# controller.net
KiCad netlist of a schematic drawn in EAGLE
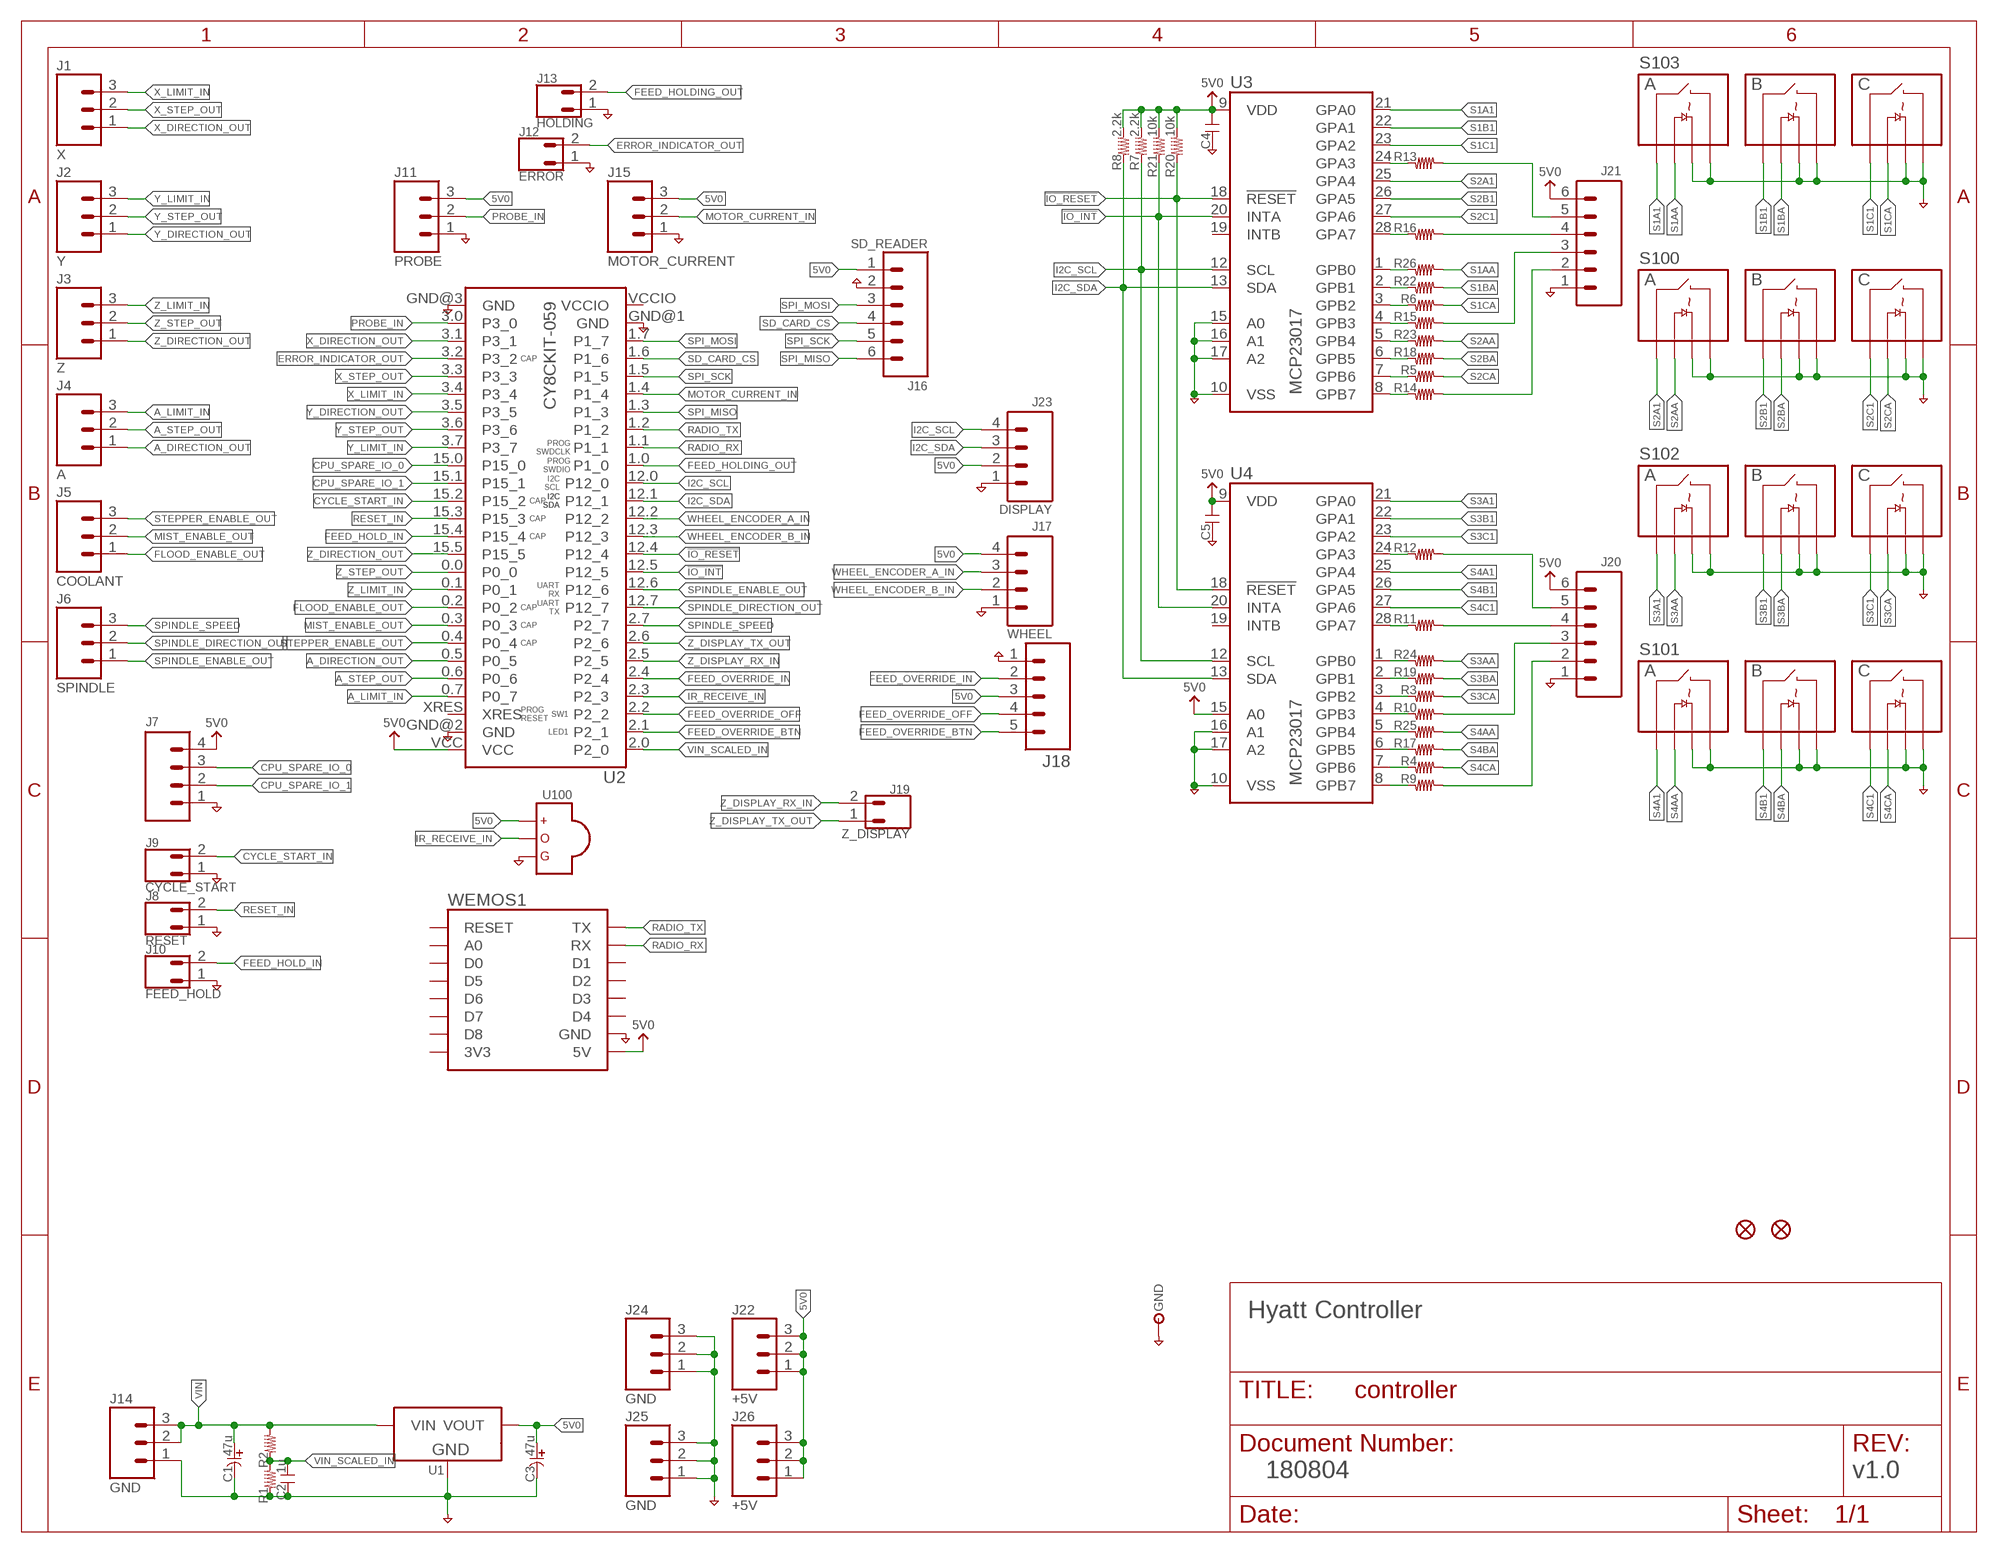
[diagram p0: schematic, sheet 1]

(export (version "E")
  (design (tool "Eeschema 10.0.6"))
  (components
    (comp (ref "C1")
      (value "47u")
      (footprint "eagle-import:E5-10")
      (libsource (lib "eagle-import") (part "C-POLARIZED-E5-10"))
    )
    (comp (ref "C2")
      (value "1u")
      (footprint "eagle-import:C0603")
      (libsource (lib "eagle-import") (part "C-0603"))
    )
    (comp (ref "C3")
      (value "47u")
      (footprint "eagle-import:E5-10")
      (libsource (lib "eagle-import") (part "C-POLARIZED-E5-10"))
    )
    (comp (ref "C4")
      (value "C-0603")
      (footprint "eagle-import:C0603")
      (libsource (lib "eagle-import") (part "C-0603"))
    )
    (comp (ref "C5")
      (value "C-0603")
      (footprint "eagle-import:C0603")
      (libsource (lib "eagle-import") (part "C-0603"))
    )
    (comp (ref "FID1")
      (value "FIDUCIAL1.5X3")
      (footprint "eagle-import:FIDUCIAL-1.5X3")
      (libsource (lib "eagle-import") (part "FIDUCIAL1.5X3"))
    )
    (comp (ref "FID2")
      (value "FIDUCIAL1.5X3")
      (footprint "eagle-import:FIDUCIAL-1.5X3")
      (libsource (lib "eagle-import") (part "FIDUCIAL1.5X3"))
    )
    (comp (ref "GND")
      (value "TESTPOINTTHRU")
      (footprint "eagle-import:TPTHRU")
      (libsource (lib "eagle-import") (part "TESTPOINTTHRU"))
    )
    (comp (ref "J1")
      (value "X")
      (footprint "eagle-import:CONN-3.81MM-KF2EDG-3")
      (libsource (lib "eagle-import") (part "CONN-03-3.81MM-PLUGIN-SCREW"))
    )
    (comp (ref "J2")
      (value "Y")
      (footprint "eagle-import:CONN-3.81MM-KF2EDG-3")
      (libsource (lib "eagle-import") (part "CONN-03-3.81MM-PLUGIN-SCREW"))
    )
    (comp (ref "J3")
      (value "Z")
      (footprint "eagle-import:CONN-3.81MM-KF2EDG-3")
      (libsource (lib "eagle-import") (part "CONN-03-3.81MM-PLUGIN-SCREW"))
    )
    (comp (ref "J4")
      (value "A")
      (footprint "eagle-import:CONN-3.81MM-KF2EDG-3")
      (libsource (lib "eagle-import") (part "CONN-03-3.81MM-PLUGIN-SCREW"))
    )
    (comp (ref "J5")
      (value "COOLANT")
      (footprint "eagle-import:CONN-3.81MM-KF2EDG-3")
      (libsource (lib "eagle-import") (part "CONN-03-3.81MM-PLUGIN-SCREW"))
    )
    (comp (ref "J6")
      (value "SPINDLE")
      (footprint "eagle-import:CONN-3.81MM-KF2EDG-3")
      (libsource (lib "eagle-import") (part "CONN-03-3.81MM-PLUGIN-SCREW"))
    )
    (comp (ref "J7")
      (value "CONN-04-0.1")
      (footprint "eagle-import:1X04")
      (libsource (lib "eagle-import") (part "CONN-04-0.1"))
    )
    (comp (ref "J8")
      (value "RESET")
      (footprint "eagle-import:CONN-.100-2")
      (libsource (lib "eagle-import") (part "CONN-02-.100-VERT-HEADER"))
    )
    (comp (ref "J9")
      (value "CYCLE_START")
      (footprint "eagle-import:CONN-.100-2")
      (libsource (lib "eagle-import") (part "CONN-02-.100-VERT-HEADER"))
    )
    (comp (ref "J10")
      (value "FEED_HOLD")
      (footprint "eagle-import:CONN-.100-2")
      (libsource (lib "eagle-import") (part "CONN-02-.100-VERT-HEADER"))
    )
    (comp (ref "J11")
      (value "PROBE")
      (footprint "eagle-import:CONN-3.81MM-KF2EDG-3")
      (libsource (lib "eagle-import") (part "CONN-03-3.81MM-PLUGIN-SCREW"))
    )
    (comp (ref "J12")
      (value "ERROR")
      (footprint "eagle-import:CONN-.100-2")
      (libsource (lib "eagle-import") (part "CONN-02-.100-VERT-HEADER"))
    )
    (comp (ref "J13")
      (value "HOLDING")
      (footprint "eagle-import:CONN-.100-2")
      (libsource (lib "eagle-import") (part "CONN-02-.100-VERT-HEADER"))
    )
    (comp (ref "J14")
      (value "GND")
      (footprint "eagle-import:CONN-3.81MM-KF2EDG-3")
      (libsource (lib "eagle-import") (part "CONN-03-3.81MM-PLUGIN-SCREW"))
    )
    (comp (ref "J15")
      (value "MOTOR_CURRENT")
      (footprint "eagle-import:CONN-3.81MM-KF2EDG-3")
      (libsource (lib "eagle-import") (part "CONN-03-3.81MM-PLUGIN-SCREW"))
    )
    (comp (ref "J16")
      (value "SD_READER")
      (footprint "eagle-import:1X06")
      (libsource (lib "eagle-import") (part "CONN-06-0.1"))
    )
    (comp (ref "J17")
      (value "WHEEL")
      (footprint "eagle-import:CONN-.100-4")
      (libsource (lib "eagle-import") (part "CONN-04-.100-VERT-HEADER"))
    )
    (comp (ref "J18")
      (value "CONN-05-PTH")
      (footprint "eagle-import:1X05")
      (libsource (lib "eagle-import") (part "CONN-05-PTH"))
    )
    (comp (ref "J19")
      (value "Z_DISPLAY")
      (footprint "eagle-import:CONN-3.81MM-KF2EDG-2")
      (libsource (lib "eagle-import") (part "CONN-02-3.81MM-PLUGIN-SCREW"))
    )
    (comp (ref "J20")
      (value "CONN-06-.100-VERT-HEADER")
      (footprint "eagle-import:CONN-.100-6")
      (libsource (lib "eagle-import") (part "CONN-06-.100-VERT-HEADER"))
    )
    (comp (ref "J21")
      (value "CONN-06-.100-VERT-HEADER")
      (footprint "eagle-import:CONN-.100-6")
      (libsource (lib "eagle-import") (part "CONN-06-.100-VERT-HEADER"))
    )
    (comp (ref "J22")
      (value "+5V")
      (footprint "eagle-import:CONN-3.81MM-KF2EDG-3")
      (libsource (lib "eagle-import") (part "CONN-03-3.81MM-PLUGIN-SCREW"))
    )
    (comp (ref "J23")
      (value "DISPLAY")
      (footprint "eagle-import:CONN-.100-4")
      (libsource (lib "eagle-import") (part "CONN-04-.100-VERT-HEADER"))
    )
    (comp (ref "J24")
      (value "GND")
      (footprint "eagle-import:CONN-3.81MM-KF2EDG-3")
      (libsource (lib "eagle-import") (part "CONN-03-3.81MM-PLUGIN-SCREW"))
    )
    (comp (ref "J25")
      (value "GND")
      (footprint "eagle-import:CONN-3.81MM-KF2EDG-3")
      (libsource (lib "eagle-import") (part "CONN-03-3.81MM-PLUGIN-SCREW"))
    )
    (comp (ref "J26")
      (value "+5V")
      (footprint "eagle-import:CONN-3.81MM-KF2EDG-3")
      (libsource (lib "eagle-import") (part "CONN-03-3.81MM-PLUGIN-SCREW"))
    )
    (comp (ref "R1")
      (value "R-0603")
      (footprint "eagle-import:R0603")
      (libsource (lib "eagle-import") (part "R-0603"))
    )
    (comp (ref "R2")
      (value "R-0603")
      (footprint "eagle-import:R0603")
      (libsource (lib "eagle-import") (part "R-0603"))
    )
    (comp (ref "R3")
      (value "R-0603")
      (footprint "eagle-import:R0603")
      (libsource (lib "eagle-import") (part "R-0603"))
    )
    (comp (ref "R4")
      (value "R-0603")
      (footprint "eagle-import:R0603")
      (libsource (lib "eagle-import") (part "R-0603"))
    )
    (comp (ref "R5")
      (value "R-0603")
      (footprint "eagle-import:R0603")
      (libsource (lib "eagle-import") (part "R-0603"))
    )
    (comp (ref "R6")
      (value "R-0603")
      (footprint "eagle-import:R0603")
      (libsource (lib "eagle-import") (part "R-0603"))
    )
    (comp (ref "R7")
      (value "2.2k")
      (footprint "eagle-import:R0603")
      (libsource (lib "eagle-import") (part "R-0603"))
    )
    (comp (ref "R8")
      (value "2.2k")
      (footprint "eagle-import:R0603")
      (libsource (lib "eagle-import") (part "R-0603"))
    )
    (comp (ref "R9")
      (value "R-0603")
      (footprint "eagle-import:R0603")
      (libsource (lib "eagle-import") (part "R-0603"))
    )
    (comp (ref "R10")
      (value "R-0603")
      (footprint "eagle-import:R0603")
      (libsource (lib "eagle-import") (part "R-0603"))
    )
    (comp (ref "R11")
      (value "R-0603")
      (footprint "eagle-import:R0603")
      (libsource (lib "eagle-import") (part "R-0603"))
    )
    (comp (ref "R12")
      (value "R-0603")
      (footprint "eagle-import:R0603")
      (libsource (lib "eagle-import") (part "R-0603"))
    )
    (comp (ref "R13")
      (value "R-0603")
      (footprint "eagle-import:R0603")
      (libsource (lib "eagle-import") (part "R-0603"))
    )
    (comp (ref "R14")
      (value "R-0603")
      (footprint "eagle-import:R0603")
      (libsource (lib "eagle-import") (part "R-0603"))
    )
    (comp (ref "R15")
      (value "R-0603")
      (footprint "eagle-import:R0603")
      (libsource (lib "eagle-import") (part "R-0603"))
    )
    (comp (ref "R16")
      (value "R-0603")
      (footprint "eagle-import:R0603")
      (libsource (lib "eagle-import") (part "R-0603"))
    )
    (comp (ref "R17")
      (value "R-0603")
      (footprint "eagle-import:R0603")
      (libsource (lib "eagle-import") (part "R-0603"))
    )
    (comp (ref "R18")
      (value "R-0603")
      (footprint "eagle-import:R0603")
      (libsource (lib "eagle-import") (part "R-0603"))
    )
    (comp (ref "R19")
      (value "R-0603")
      (footprint "eagle-import:R0603")
      (libsource (lib "eagle-import") (part "R-0603"))
    )
    (comp (ref "R20")
      (value "10k")
      (footprint "eagle-import:R0603")
      (libsource (lib "eagle-import") (part "R-0603"))
    )
    (comp (ref "R21")
      (value "10k")
      (footprint "eagle-import:R0603")
      (libsource (lib "eagle-import") (part "R-0603"))
    )
    (comp (ref "R22")
      (value "R-0603")
      (footprint "eagle-import:R0603")
      (libsource (lib "eagle-import") (part "R-0603"))
    )
    (comp (ref "R23")
      (value "R-0603")
      (footprint "eagle-import:R0603")
      (libsource (lib "eagle-import") (part "R-0603"))
    )
    (comp (ref "R24")
      (value "R-0603")
      (footprint "eagle-import:R0603")
      (libsource (lib "eagle-import") (part "R-0603"))
    )
    (comp (ref "R25")
      (value "R-0603")
      (footprint "eagle-import:R0603")
      (libsource (lib "eagle-import") (part "R-0603"))
    )
    (comp (ref "R26")
      (value "R-0603")
      (footprint "eagle-import:R0603")
      (libsource (lib "eagle-import") (part "R-0603"))
    )
    (comp (ref "S100")
      (value "SWITCH-DTMF-3-LED")
      (footprint "eagle-import:SWITCH-DTMF-3-LED")
      (libsource (lib "eagle-import") (part "SWITCH-DTMF-3-LED"))
    )
    (comp (ref "S101")
      (value "SWITCH-DTMF-3-LED")
      (footprint "eagle-import:SWITCH-DTMF-3-LED")
      (libsource (lib "eagle-import") (part "SWITCH-DTMF-3-LED"))
    )
    (comp (ref "S102")
      (value "SWITCH-DTMF-3-LED")
      (footprint "eagle-import:SWITCH-DTMF-3-LED")
      (libsource (lib "eagle-import") (part "SWITCH-DTMF-3-LED"))
    )
    (comp (ref "S103")
      (value "SWITCH-DTMF-3-LED")
      (footprint "eagle-import:SWITCH-DTMF-3-LED")
      (libsource (lib "eagle-import") (part "SWITCH-DTMF-3-LED"))
    )
    (comp (ref "U1")
      (value "VREG-SIP3")
      (footprint "eagle-import:VREG-SIP3")
      (libsource (lib "eagle-import") (part "VREG-SIP3"))
    )
    (comp (ref "U2")
      (value "BOARD-PSOC-CY8CKIT-059")
      (footprint "eagle-import:BOARD-PSOC-CY8CKIT-059")
      (libsource (lib "eagle-import") (part "BOARD-PSOC-CY8CKIT-059"))
    )
    (comp (ref "U3")
      (value "IO-MCP23017SO")
      (footprint "eagle-import:SO28W")
      (fields (field (name "MF") "MICROCHIP") (field (name "MPN") "MCP23017-E/SO"))
      (libsource (lib "eagle-import") (part "IO-MCP23017SO"))
    )
    (comp (ref "U4")
      (value "IO-MCP23017SO")
      (footprint "eagle-import:SO28W")
      (fields (field (name "MF") "MICROCHIP") (field (name "MPN") "MCP23017-E/SO"))
      (libsource (lib "eagle-import") (part "IO-MCP23017SO"))
    )
    (comp (ref "U100")
      (value "SENSOR-IR-THRU")
      (footprint "eagle-import:IRDETECTOR-THRU")
      (libsource (lib "eagle-import") (part "SENSOR-IR-THRU"))
    )
    (comp (ref "WEMOS1")
      (value "RADIO-WEMOS-D1-MINI")
      (footprint "eagle-import:WEMOS-D1-MINI")
      (libsource (lib "eagle-import") (part "RADIO-WEMOS-D1-MINI"))
    )
  )
  (nets
    (net (code "1") (name "/~{IO_INT}") (class "Default")
      (node (ref "R21") (pin "1") (pinfunction "1_1") (pintype "passive"))
      (node (ref "U2") (pin "12.5") (pinfunction "P12_5_12.5") (pintype "bidirectional"))
      (node (ref "U3") (pin "20") (pinfunction "INTA_20") (pintype "output"))
      (node (ref "U4") (pin "20") (pinfunction "INTA_20") (pintype "output"))
    )
    (net (code "2") (name "/~{IO_RESET}") (class "Default")
      (node (ref "R20") (pin "1") (pinfunction "1_1") (pintype "passive"))
      (node (ref "U2") (pin "12.4") (pinfunction "P12_4_12.4") (pintype "bidirectional"))
      (node (ref "U3") (pin "18") (pinfunction "~{RESET}_18") (pintype "input"))
      (node (ref "U4") (pin "18") (pinfunction "~{RESET}_18") (pintype "input"))
    )
    (net (code "3") (name "5V0") (class "Default")
      (node (ref "C3") (pin "+") (pinfunction "+_+") (pintype "passive"))
      (node (ref "C4") (pin "1") (pinfunction "1_1") (pintype "passive"))
      (node (ref "C5") (pin "1") (pinfunction "1_1") (pintype "passive"))
      (node (ref "J11") (pin "3") (pinfunction "3_3") (pintype "passive"))
      (node (ref "J15") (pin "3") (pinfunction "3_3") (pintype "passive"))
      (node (ref "J16") (pin "1") (pinfunction "1_1") (pintype "passive"))
      (node (ref "J17") (pin "4") (pinfunction "4_4") (pintype "passive"))
      (node (ref "J18") (pin "3") (pinfunction "3_3") (pintype "passive"))
      (node (ref "J20") (pin "6") (pinfunction "6_6") (pintype "passive"))
      (node (ref "J21") (pin "6") (pinfunction "6_6") (pintype "passive"))
      (node (ref "J22") (pin "1") (pinfunction "1_1") (pintype "passive"))
      (node (ref "J22") (pin "2") (pinfunction "2_2") (pintype "passive"))
      (node (ref "J22") (pin "3") (pinfunction "3_3") (pintype "passive"))
      (node (ref "J23") (pin "2") (pinfunction "2_2") (pintype "passive"))
      (node (ref "J26") (pin "1") (pinfunction "1_1") (pintype "passive"))
      (node (ref "J26") (pin "2") (pinfunction "2_2") (pintype "passive"))
      (node (ref "J26") (pin "3") (pinfunction "3_3") (pintype "passive"))
      (node (ref "J7") (pin "4") (pinfunction "4_4") (pintype "passive"))
      (node (ref "R20") (pin "2") (pinfunction "2_2") (pintype "passive"))
      (node (ref "R21") (pin "2") (pinfunction "2_2") (pintype "passive"))
      (node (ref "R7") (pin "2") (pinfunction "2_2") (pintype "passive"))
      (node (ref "R8") (pin "2") (pinfunction "2_2") (pintype "passive"))
      (node (ref "U1") (pin "3") (pinfunction "VOUT_3") (pintype "bidirectional"))
      (node (ref "U100") (pin "VCC") (pinfunction "VCC_VCC") (pintype "bidirectional"))
      (node (ref "U2") (pin "VCC") (pinfunction "VCC_VCC") (pintype "bidirectional"))
      (node (ref "U3") (pin "9") (pinfunction "VDD_9") (pintype "power_in"))
      (node (ref "U4") (pin "15") (pinfunction "A0_15") (pintype "input"))
      (node (ref "U4") (pin "9") (pinfunction "VDD_9") (pintype "power_in"))
      (node (ref "WEMOS1") (pin "5V") (pinfunction "5V_5V") (pintype "bidirectional"))
    )
    (net (code "4") (name "A_DIRECTION_OUT") (class "Default")
      (node (ref "J4") (pin "1") (pinfunction "1_1") (pintype "passive"))
      (node (ref "U2") (pin "0.5") (pinfunction "P0_5_0.5") (pintype "bidirectional"))
    )
    (net (code "5") (name "A_LIMIT_IN") (class "Default")
      (node (ref "J4") (pin "3") (pinfunction "3_3") (pintype "passive"))
      (node (ref "U2") (pin "0.7") (pinfunction "P0_7_0.7") (pintype "bidirectional"))
    )
    (net (code "6") (name "A_STEP_OUT") (class "Default")
      (node (ref "J4") (pin "2") (pinfunction "2_2") (pintype "passive"))
      (node (ref "U2") (pin "0.6") (pinfunction "P0_6_0.6") (pintype "bidirectional"))
    )
    (net (code "7") (name "CPU_SPARE_IO_0") (class "Default")
      (node (ref "J7") (pin "3") (pinfunction "3_3") (pintype "passive"))
      (node (ref "U2") (pin "15.0") (pinfunction "P15_0_15.0") (pintype "bidirectional"))
    )
    (net (code "8") (name "CPU_SPARE_IO_1") (class "Default")
      (node (ref "J7") (pin "2") (pinfunction "2_2") (pintype "passive"))
      (node (ref "U2") (pin "15.1") (pinfunction "P15_1_15.1") (pintype "bidirectional"))
    )
    (net (code "9") (name "CYCLE_START_IN") (class "Default")
      (node (ref "J9") (pin "2") (pinfunction "2_2") (pintype "passive"))
      (node (ref "U2") (pin "15.2") (pinfunction "P15_2_15.2") (pintype "bidirectional"))
    )
    (net (code "10") (name "ERROR_INDICATOR_OUT") (class "Default")
      (node (ref "J12") (pin "2") (pinfunction "2_2") (pintype "passive"))
      (node (ref "U2") (pin "3.2") (pinfunction "P3_2_3.2") (pintype "bidirectional"))
    )
    (net (code "11") (name "FEED_HOLDING_OUT") (class "Default")
      (node (ref "J13") (pin "2") (pinfunction "2_2") (pintype "passive"))
      (node (ref "U2") (pin "1.0") (pinfunction "P1_0_1.0") (pintype "bidirectional"))
    )
    (net (code "12") (name "FEED_HOLD_IN") (class "Default")
      (node (ref "J10") (pin "2") (pinfunction "2_2") (pintype "passive"))
      (node (ref "U2") (pin "15.4") (pinfunction "P15_4_15.4") (pintype "bidirectional"))
    )
    (net (code "13") (name "FEED_OVERRIDE_BTN") (class "Default")
      (node (ref "J18") (pin "5") (pinfunction "5_5") (pintype "passive"))
      (node (ref "U2") (pin "2.1") (pinfunction "P2_1_2.1") (pintype "bidirectional"))
    )
    (net (code "14") (name "FEED_OVERRIDE_IN") (class "Default")
      (node (ref "J18") (pin "2") (pinfunction "2_2") (pintype "passive"))
      (node (ref "U2") (pin "2.4") (pinfunction "P2_4_2.4") (pintype "bidirectional"))
    )
    (net (code "15") (name "FEED_OVERRIDE_OFF") (class "Default")
      (node (ref "J18") (pin "4") (pinfunction "4_4") (pintype "passive"))
      (node (ref "U2") (pin "2.2") (pinfunction "P2_2_2.2") (pintype "bidirectional"))
    )
    (net (code "16") (name "FLOOD_ENABLE_OUT") (class "Default")
      (node (ref "J5") (pin "1") (pinfunction "1_1") (pintype "passive"))
      (node (ref "U2") (pin "0.2") (pinfunction "P0_2_0.2") (pintype "bidirectional"))
    )
    (net (code "17") (name "GND") (class "Default")
      (node (ref "C1") (pin "-") (pinfunction "-_-") (pintype "passive"))
      (node (ref "C2") (pin "2") (pinfunction "2_2") (pintype "passive"))
      (node (ref "C3") (pin "-") (pinfunction "-_-") (pintype "passive"))
      (node (ref "C4") (pin "2") (pinfunction "2_2") (pintype "passive"))
      (node (ref "C5") (pin "2") (pinfunction "2_2") (pintype "passive"))
      (node (ref "GND") (pin "1") (pinfunction "P$1_1") (pintype "bidirectional"))
      (node (ref "J10") (pin "1") (pinfunction "1_1") (pintype "passive"))
      (node (ref "J11") (pin "1") (pinfunction "1_1") (pintype "passive"))
      (node (ref "J12") (pin "1") (pinfunction "1_1") (pintype "passive"))
      (node (ref "J13") (pin "1") (pinfunction "1_1") (pintype "passive"))
      (node (ref "J14") (pin "1") (pinfunction "1_1") (pintype "passive"))
      (node (ref "J15") (pin "1") (pinfunction "1_1") (pintype "passive"))
      (node (ref "J16") (pin "2") (pinfunction "2_2") (pintype "passive"))
      (node (ref "J17") (pin "1") (pinfunction "1_1") (pintype "passive"))
      (node (ref "J18") (pin "1") (pinfunction "1_1") (pintype "passive"))
      (node (ref "J20") (pin "1") (pinfunction "1_1") (pintype "passive"))
      (node (ref "J21") (pin "1") (pinfunction "1_1") (pintype "passive"))
      (node (ref "J23") (pin "1") (pinfunction "1_1") (pintype "passive"))
      (node (ref "J24") (pin "1") (pinfunction "1_1") (pintype "passive"))
      (node (ref "J24") (pin "2") (pinfunction "2_2") (pintype "passive"))
      (node (ref "J24") (pin "3") (pinfunction "3_3") (pintype "passive"))
      (node (ref "J25") (pin "1") (pinfunction "1_1") (pintype "passive"))
      (node (ref "J25") (pin "2") (pinfunction "2_2") (pintype "passive"))
      (node (ref "J25") (pin "3") (pinfunction "3_3") (pintype "passive"))
      (node (ref "J7") (pin "1") (pinfunction "1_1") (pintype "passive"))
      (node (ref "J8") (pin "1") (pinfunction "1_1") (pintype "passive"))
      (node (ref "J9") (pin "1") (pinfunction "1_1") (pintype "passive"))
      (node (ref "R1") (pin "1") (pinfunction "1_1") (pintype "passive"))
      (node (ref "S100") (pin "A_2") (pinfunction "A_2_A_2") (pintype "bidirectional"))
      (node (ref "S100") (pin "A_C") (pinfunction "A_C_A_C") (pintype "bidirectional"))
      (node (ref "S100") (pin "B_2") (pinfunction "B_2_B_2") (pintype "bidirectional"))
      (node (ref "S100") (pin "B_C") (pinfunction "B_C_B_C") (pintype "bidirectional"))
      (node (ref "S100") (pin "C_2") (pinfunction "C_2_C_2") (pintype "bidirectional"))
      (node (ref "S100") (pin "C_C") (pinfunction "C_C_C_C") (pintype "bidirectional"))
      (node (ref "S101") (pin "A_2") (pinfunction "A_2_A_2") (pintype "bidirectional"))
      (node (ref "S101") (pin "A_C") (pinfunction "A_C_A_C") (pintype "bidirectional"))
      (node (ref "S101") (pin "B_2") (pinfunction "B_2_B_2") (pintype "bidirectional"))
      (node (ref "S101") (pin "B_C") (pinfunction "B_C_B_C") (pintype "bidirectional"))
      (node (ref "S101") (pin "C_2") (pinfunction "C_2_C_2") (pintype "bidirectional"))
      (node (ref "S101") (pin "C_C") (pinfunction "C_C_C_C") (pintype "bidirectional"))
      (node (ref "S102") (pin "A_2") (pinfunction "A_2_A_2") (pintype "bidirectional"))
      (node (ref "S102") (pin "A_C") (pinfunction "A_C_A_C") (pintype "bidirectional"))
      (node (ref "S102") (pin "B_2") (pinfunction "B_2_B_2") (pintype "bidirectional"))
      (node (ref "S102") (pin "B_C") (pinfunction "B_C_B_C") (pintype "bidirectional"))
      (node (ref "S102") (pin "C_2") (pinfunction "C_2_C_2") (pintype "bidirectional"))
      (node (ref "S102") (pin "C_C") (pinfunction "C_C_C_C") (pintype "bidirectional"))
      (node (ref "S103") (pin "A_2") (pinfunction "A_2_A_2") (pintype "bidirectional"))
      (node (ref "S103") (pin "A_C") (pinfunction "A_C_A_C") (pintype "bidirectional"))
      (node (ref "S103") (pin "B_2") (pinfunction "B_2_B_2") (pintype "bidirectional"))
      (node (ref "S103") (pin "B_C") (pinfunction "B_C_B_C") (pintype "bidirectional"))
      (node (ref "S103") (pin "C_2") (pinfunction "C_2_C_2") (pintype "bidirectional"))
      (node (ref "S103") (pin "C_C") (pinfunction "C_C_C_C") (pintype "bidirectional"))
      (node (ref "U1") (pin "2") (pinfunction "GND_2") (pintype "bidirectional"))
      (node (ref "U100") (pin "GND") (pinfunction "GND_GND") (pintype "bidirectional"))
      (node (ref "U2") (pin "GND@1") (pinfunction "GND_GND@1") (pintype "bidirectional"))
      (node (ref "U2") (pin "GND@2") (pinfunction "GND_GND@2") (pintype "bidirectional"))
      (node (ref "U2") (pin "GND@3") (pinfunction "GND_GND@3") (pintype "bidirectional"))
      (node (ref "U3") (pin "10") (pinfunction "VSS_10") (pintype "power_in"))
      (node (ref "U3") (pin "15") (pinfunction "A0_15") (pintype "input"))
      (node (ref "U3") (pin "16") (pinfunction "A1_16") (pintype "input"))
      (node (ref "U3") (pin "17") (pinfunction "A2_17") (pintype "input"))
      (node (ref "U4") (pin "10") (pinfunction "VSS_10") (pintype "power_in"))
      (node (ref "U4") (pin "16") (pinfunction "A1_16") (pintype "input"))
      (node (ref "U4") (pin "17") (pinfunction "A2_17") (pintype "input"))
      (node (ref "WEMOS1") (pin "GND") (pinfunction "GND_GND") (pintype "bidirectional"))
    )
    (net (code "18") (name "I2C_SCL") (class "Default")
      (node (ref "J23") (pin "4") (pinfunction "4_4") (pintype "passive"))
      (node (ref "R7") (pin "1") (pinfunction "1_1") (pintype "passive"))
      (node (ref "U2") (pin "12.0") (pinfunction "P12_0_12.0") (pintype "bidirectional"))
      (node (ref "U3") (pin "12") (pinfunction "SCL_12") (pintype "input"))
      (node (ref "U4") (pin "12") (pinfunction "SCL_12") (pintype "input"))
    )
    (net (code "19") (name "I2C_SDA") (class "Default")
      (node (ref "J23") (pin "3") (pinfunction "3_3") (pintype "passive"))
      (node (ref "R8") (pin "1") (pinfunction "1_1") (pintype "passive"))
      (node (ref "U2") (pin "12.1") (pinfunction "P12_1_12.1") (pintype "bidirectional"))
      (node (ref "U3") (pin "13") (pinfunction "SDA_13") (pintype "bidirectional"))
      (node (ref "U4") (pin "13") (pinfunction "SDA_13") (pintype "bidirectional"))
    )
    (net (code "20") (name "IR_RECEIVE_IN") (class "Default")
      (node (ref "U100") (pin "VOUT") (pinfunction "VOUT_VOUT") (pintype "bidirectional"))
      (node (ref "U2") (pin "2.3") (pinfunction "P2_3_2.3") (pintype "bidirectional"))
    )
    (net (code "21") (name "MIST_ENABLE_OUT") (class "Default")
      (node (ref "J5") (pin "2") (pinfunction "2_2") (pintype "passive"))
      (node (ref "U2") (pin "0.3") (pinfunction "P0_3_0.3") (pintype "bidirectional"))
    )
    (net (code "22") (name "MOTOR_CURRENT_IN") (class "Default")
      (node (ref "J15") (pin "2") (pinfunction "2_2") (pintype "passive"))
      (node (ref "U2") (pin "1.4") (pinfunction "P1_4_1.4") (pintype "bidirectional"))
    )
    (net (code "23") (name "Net-(J20-Pad2)") (class "Default")
      (node (ref "J20") (pin "2") (pinfunction "2_2") (pintype "passive"))
      (node (ref "R9") (pin "2") (pinfunction "2_2") (pintype "passive"))
    )
    (net (code "24") (name "Net-(J20-Pad3)") (class "Default")
      (node (ref "J20") (pin "3") (pinfunction "3_3") (pintype "passive"))
      (node (ref "R10") (pin "2") (pinfunction "2_2") (pintype "passive"))
    )
    (net (code "25") (name "Net-(J20-Pad4)") (class "Default")
      (node (ref "J20") (pin "4") (pinfunction "4_4") (pintype "passive"))
      (node (ref "R11") (pin "2") (pinfunction "2_2") (pintype "passive"))
    )
    (net (code "26") (name "Net-(J20-Pad5)") (class "Default")
      (node (ref "J20") (pin "5") (pinfunction "5_5") (pintype "passive"))
      (node (ref "R12") (pin "2") (pinfunction "2_2") (pintype "passive"))
    )
    (net (code "27") (name "Net-(J21-Pad2)") (class "Default")
      (node (ref "J21") (pin "2") (pinfunction "2_2") (pintype "passive"))
      (node (ref "R14") (pin "2") (pinfunction "2_2") (pintype "passive"))
    )
    (net (code "28") (name "Net-(J21-Pad3)") (class "Default")
      (node (ref "J21") (pin "3") (pinfunction "3_3") (pintype "passive"))
      (node (ref "R15") (pin "2") (pinfunction "2_2") (pintype "passive"))
    )
    (net (code "29") (name "Net-(J21-Pad4)") (class "Default")
      (node (ref "J21") (pin "4") (pinfunction "4_4") (pintype "passive"))
      (node (ref "R16") (pin "2") (pinfunction "2_2") (pintype "passive"))
    )
    (net (code "30") (name "Net-(J21-Pad5)") (class "Default")
      (node (ref "J21") (pin "5") (pinfunction "5_5") (pintype "passive"))
      (node (ref "R13") (pin "2") (pinfunction "2_2") (pintype "passive"))
    )
    (net (code "31") (name "Net-(U3-GPA3)") (class "Default")
      (node (ref "R13") (pin "1") (pinfunction "1_1") (pintype "passive"))
      (node (ref "U3") (pin "24") (pinfunction "GPA3_24") (pintype "bidirectional"))
    )
    (net (code "32") (name "Net-(U3-GPA7)") (class "Default")
      (node (ref "R16") (pin "1") (pinfunction "1_1") (pintype "passive"))
      (node (ref "U3") (pin "28") (pinfunction "GPA7_28") (pintype "bidirectional"))
    )
    (net (code "33") (name "Net-(U3-GPB0)") (class "Default")
      (node (ref "R26") (pin "1") (pinfunction "1_1") (pintype "passive"))
      (node (ref "U3") (pin "1") (pinfunction "GPB0_1") (pintype "bidirectional"))
    )
    (net (code "34") (name "Net-(U3-GPB1)") (class "Default")
      (node (ref "R22") (pin "1") (pinfunction "1_1") (pintype "passive"))
      (node (ref "U3") (pin "2") (pinfunction "GPB1_2") (pintype "bidirectional"))
    )
    (net (code "35") (name "Net-(U3-GPB2)") (class "Default")
      (node (ref "R6") (pin "1") (pinfunction "1_1") (pintype "passive"))
      (node (ref "U3") (pin "3") (pinfunction "GPB2_3") (pintype "bidirectional"))
    )
    (net (code "36") (name "Net-(U3-GPB3)") (class "Default")
      (node (ref "R15") (pin "1") (pinfunction "1_1") (pintype "passive"))
      (node (ref "U3") (pin "4") (pinfunction "GPB3_4") (pintype "bidirectional"))
    )
    (net (code "37") (name "Net-(U3-GPB4)") (class "Default")
      (node (ref "R23") (pin "1") (pinfunction "1_1") (pintype "passive"))
      (node (ref "U3") (pin "5") (pinfunction "GPB4_5") (pintype "bidirectional"))
    )
    (net (code "38") (name "Net-(U3-GPB5)") (class "Default")
      (node (ref "R18") (pin "1") (pinfunction "1_1") (pintype "passive"))
      (node (ref "U3") (pin "6") (pinfunction "GPB5_6") (pintype "bidirectional"))
    )
    (net (code "39") (name "Net-(U3-GPB6)") (class "Default")
      (node (ref "R5") (pin "1") (pinfunction "1_1") (pintype "passive"))
      (node (ref "U3") (pin "7") (pinfunction "GPB6_7") (pintype "bidirectional"))
    )
    (net (code "40") (name "Net-(U3-GPB7)") (class "Default")
      (node (ref "R14") (pin "1") (pinfunction "1_1") (pintype "passive"))
      (node (ref "U3") (pin "8") (pinfunction "GPB7_8") (pintype "bidirectional"))
    )
    (net (code "41") (name "Net-(U4-GPA3)") (class "Default")
      (node (ref "R12") (pin "1") (pinfunction "1_1") (pintype "passive"))
      (node (ref "U4") (pin "24") (pinfunction "GPA3_24") (pintype "bidirectional"))
    )
    (net (code "42") (name "Net-(U4-GPA7)") (class "Default")
      (node (ref "R11") (pin "1") (pinfunction "1_1") (pintype "passive"))
      (node (ref "U4") (pin "28") (pinfunction "GPA7_28") (pintype "bidirectional"))
    )
    (net (code "43") (name "Net-(U4-GPB0)") (class "Default")
      (node (ref "R24") (pin "1") (pinfunction "1_1") (pintype "passive"))
      (node (ref "U4") (pin "1") (pinfunction "GPB0_1") (pintype "bidirectional"))
    )
    (net (code "44") (name "Net-(U4-GPB1)") (class "Default")
      (node (ref "R19") (pin "1") (pinfunction "1_1") (pintype "passive"))
      (node (ref "U4") (pin "2") (pinfunction "GPB1_2") (pintype "bidirectional"))
    )
    (net (code "45") (name "Net-(U4-GPB2)") (class "Default")
      (node (ref "R3") (pin "1") (pinfunction "1_1") (pintype "passive"))
      (node (ref "U4") (pin "3") (pinfunction "GPB2_3") (pintype "bidirectional"))
    )
    (net (code "46") (name "Net-(U4-GPB3)") (class "Default")
      (node (ref "R10") (pin "1") (pinfunction "1_1") (pintype "passive"))
      (node (ref "U4") (pin "4") (pinfunction "GPB3_4") (pintype "bidirectional"))
    )
    (net (code "47") (name "Net-(U4-GPB4)") (class "Default")
      (node (ref "R25") (pin "1") (pinfunction "1_1") (pintype "passive"))
      (node (ref "U4") (pin "5") (pinfunction "GPB4_5") (pintype "bidirectional"))
    )
    (net (code "48") (name "Net-(U4-GPB5)") (class "Default")
      (node (ref "R17") (pin "1") (pinfunction "1_1") (pintype "passive"))
      (node (ref "U4") (pin "6") (pinfunction "GPB5_6") (pintype "bidirectional"))
    )
    (net (code "49") (name "Net-(U4-GPB6)") (class "Default")
      (node (ref "R4") (pin "1") (pinfunction "1_1") (pintype "passive"))
      (node (ref "U4") (pin "7") (pinfunction "GPB6_7") (pintype "bidirectional"))
    )
    (net (code "50") (name "Net-(U4-GPB7)") (class "Default")
      (node (ref "R9") (pin "1") (pinfunction "1_1") (pintype "passive"))
      (node (ref "U4") (pin "8") (pinfunction "GPB7_8") (pintype "bidirectional"))
    )
    (net (code "51") (name "PROBE_IN") (class "Default")
      (node (ref "J11") (pin "2") (pinfunction "2_2") (pintype "passive"))
      (node (ref "U2") (pin "3.0") (pinfunction "P3_0_3.0") (pintype "bidirectional"))
    )
    (net (code "52") (name "RADIO_RX") (class "Default")
      (node (ref "U2") (pin "1.1") (pinfunction "P1_1_1.1") (pintype "bidirectional"))
      (node (ref "WEMOS1") (pin "RX") (pinfunction "RX_RX") (pintype "bidirectional"))
    )
    (net (code "53") (name "RADIO_TX") (class "Default")
      (node (ref "U2") (pin "1.2") (pinfunction "P1_2_1.2") (pintype "bidirectional"))
      (node (ref "WEMOS1") (pin "TX") (pinfunction "TX_TX") (pintype "bidirectional"))
    )
    (net (code "54") (name "RESET_IN") (class "Default")
      (node (ref "J8") (pin "2") (pinfunction "2_2") (pintype "passive"))
      (node (ref "U2") (pin "15.3") (pinfunction "P15_3_15.3") (pintype "bidirectional"))
    )
    (net (code "55") (name "S1A1") (class "Default")
      (node (ref "S103") (pin "A_1") (pinfunction "A_1_A_1") (pintype "bidirectional"))
      (node (ref "U3") (pin "21") (pinfunction "GPA0_21") (pintype "bidirectional"))
    )
    (net (code "56") (name "S1AA") (class "Default")
      (node (ref "R26") (pin "2") (pinfunction "2_2") (pintype "passive"))
      (node (ref "S103") (pin "A_A") (pinfunction "A_A_A_A") (pintype "bidirectional"))
    )
    (net (code "57") (name "S1B1") (class "Default")
      (node (ref "S103") (pin "B_1") (pinfunction "B_1_B_1") (pintype "bidirectional"))
      (node (ref "U3") (pin "22") (pinfunction "GPA1_22") (pintype "bidirectional"))
    )
    (net (code "58") (name "S1BA") (class "Default")
      (node (ref "R22") (pin "2") (pinfunction "2_2") (pintype "passive"))
      (node (ref "S103") (pin "B_A") (pinfunction "B_A_B_A") (pintype "bidirectional"))
    )
    (net (code "59") (name "S1C1") (class "Default")
      (node (ref "S103") (pin "C_1") (pinfunction "C_1_C_1") (pintype "bidirectional"))
      (node (ref "U3") (pin "23") (pinfunction "GPA2_23") (pintype "bidirectional"))
    )
    (net (code "60") (name "S1CA") (class "Default")
      (node (ref "R6") (pin "2") (pinfunction "2_2") (pintype "passive"))
      (node (ref "S103") (pin "C_A") (pinfunction "C_A_C_A") (pintype "bidirectional"))
    )
    (net (code "61") (name "S2A1") (class "Default")
      (node (ref "S100") (pin "A_1") (pinfunction "A_1_A_1") (pintype "bidirectional"))
      (node (ref "U3") (pin "25") (pinfunction "GPA4_25") (pintype "bidirectional"))
    )
    (net (code "62") (name "S2AA") (class "Default")
      (node (ref "R23") (pin "2") (pinfunction "2_2") (pintype "passive"))
      (node (ref "S100") (pin "A_A") (pinfunction "A_A_A_A") (pintype "bidirectional"))
    )
    (net (code "63") (name "S2B1") (class "Default")
      (node (ref "S100") (pin "B_1") (pinfunction "B_1_B_1") (pintype "bidirectional"))
      (node (ref "U3") (pin "26") (pinfunction "GPA5_26") (pintype "bidirectional"))
    )
    (net (code "64") (name "S2BA") (class "Default")
      (node (ref "R18") (pin "2") (pinfunction "2_2") (pintype "passive"))
      (node (ref "S100") (pin "B_A") (pinfunction "B_A_B_A") (pintype "bidirectional"))
    )
    (net (code "65") (name "S2C1") (class "Default")
      (node (ref "S100") (pin "C_1") (pinfunction "C_1_C_1") (pintype "bidirectional"))
      (node (ref "U3") (pin "27") (pinfunction "GPA6_27") (pintype "bidirectional"))
    )
    (net (code "66") (name "S2CA") (class "Default")
      (node (ref "R5") (pin "2") (pinfunction "2_2") (pintype "passive"))
      (node (ref "S100") (pin "C_A") (pinfunction "C_A_C_A") (pintype "bidirectional"))
    )
    (net (code "67") (name "S3A1") (class "Default")
      (node (ref "S102") (pin "A_1") (pinfunction "A_1_A_1") (pintype "bidirectional"))
      (node (ref "U4") (pin "21") (pinfunction "GPA0_21") (pintype "bidirectional"))
    )
    (net (code "68") (name "S3AA") (class "Default")
      (node (ref "R24") (pin "2") (pinfunction "2_2") (pintype "passive"))
      (node (ref "S102") (pin "A_A") (pinfunction "A_A_A_A") (pintype "bidirectional"))
    )
    (net (code "69") (name "S3B1") (class "Default")
      (node (ref "S102") (pin "B_1") (pinfunction "B_1_B_1") (pintype "bidirectional"))
      (node (ref "U4") (pin "22") (pinfunction "GPA1_22") (pintype "bidirectional"))
    )
    (net (code "70") (name "S3BA") (class "Default")
      (node (ref "R19") (pin "2") (pinfunction "2_2") (pintype "passive"))
      (node (ref "S102") (pin "B_A") (pinfunction "B_A_B_A") (pintype "bidirectional"))
    )
    (net (code "71") (name "S3C1") (class "Default")
      (node (ref "S102") (pin "C_1") (pinfunction "C_1_C_1") (pintype "bidirectional"))
      (node (ref "U4") (pin "23") (pinfunction "GPA2_23") (pintype "bidirectional"))
    )
    (net (code "72") (name "S3CA") (class "Default")
      (node (ref "R3") (pin "2") (pinfunction "2_2") (pintype "passive"))
      (node (ref "S102") (pin "C_A") (pinfunction "C_A_C_A") (pintype "bidirectional"))
    )
    (net (code "73") (name "S4A1") (class "Default")
      (node (ref "S101") (pin "A_1") (pinfunction "A_1_A_1") (pintype "bidirectional"))
      (node (ref "U4") (pin "25") (pinfunction "GPA4_25") (pintype "bidirectional"))
    )
    (net (code "74") (name "S4AA") (class "Default")
      (node (ref "R25") (pin "2") (pinfunction "2_2") (pintype "passive"))
      (node (ref "S101") (pin "A_A") (pinfunction "A_A_A_A") (pintype "bidirectional"))
    )
    (net (code "75") (name "S4B1") (class "Default")
      (node (ref "S101") (pin "B_1") (pinfunction "B_1_B_1") (pintype "bidirectional"))
      (node (ref "U4") (pin "26") (pinfunction "GPA5_26") (pintype "bidirectional"))
    )
    (net (code "76") (name "S4BA") (class "Default")
      (node (ref "R17") (pin "2") (pinfunction "2_2") (pintype "passive"))
      (node (ref "S101") (pin "B_A") (pinfunction "B_A_B_A") (pintype "bidirectional"))
    )
    (net (code "77") (name "S4C1") (class "Default")
      (node (ref "S101") (pin "C_1") (pinfunction "C_1_C_1") (pintype "bidirectional"))
      (node (ref "U4") (pin "27") (pinfunction "GPA6_27") (pintype "bidirectional"))
    )
    (net (code "78") (name "S4CA") (class "Default")
      (node (ref "R4") (pin "2") (pinfunction "2_2") (pintype "passive"))
      (node (ref "S101") (pin "C_A") (pinfunction "C_A_C_A") (pintype "bidirectional"))
    )
    (net (code "79") (name "SD_CARD_CS") (class "Default")
      (node (ref "J16") (pin "4") (pinfunction "4_4") (pintype "passive"))
      (node (ref "U2") (pin "1.6") (pinfunction "P1_6_1.6") (pintype "bidirectional"))
    )
    (net (code "80") (name "SPINDLE_DIRECTION_OUT") (class "Default")
      (node (ref "J6") (pin "2") (pinfunction "2_2") (pintype "passive"))
      (node (ref "U2") (pin "12.7") (pinfunction "P12_7_12.7") (pintype "bidirectional"))
    )
    (net (code "81") (name "SPINDLE_ENABLE_OUT") (class "Default")
      (node (ref "J6") (pin "1") (pinfunction "1_1") (pintype "passive"))
      (node (ref "U2") (pin "12.6") (pinfunction "P12_6_12.6") (pintype "bidirectional"))
    )
    (net (code "82") (name "SPINDLE_SPEED") (class "Default")
      (node (ref "J6") (pin "3") (pinfunction "3_3") (pintype "passive"))
      (node (ref "U2") (pin "2.7") (pinfunction "P2_7_2.7") (pintype "bidirectional"))
    )
    (net (code "83") (name "SPI_MISO") (class "Default")
      (node (ref "J16") (pin "6") (pinfunction "6_6") (pintype "passive"))
      (node (ref "U2") (pin "1.3") (pinfunction "P1_3_1.3") (pintype "bidirectional"))
    )
    (net (code "84") (name "SPI_MOSI") (class "Default")
      (node (ref "J16") (pin "3") (pinfunction "3_3") (pintype "passive"))
      (node (ref "U2") (pin "1.7") (pinfunction "P1_7_1.7") (pintype "bidirectional"))
    )
    (net (code "85") (name "SPI_SCK") (class "Default")
      (node (ref "J16") (pin "5") (pinfunction "5_5") (pintype "passive"))
      (node (ref "U2") (pin "1.5") (pinfunction "P1_5_1.5") (pintype "bidirectional"))
    )
    (net (code "86") (name "STEPPER_ENABLE_OUT") (class "Default")
      (node (ref "J5") (pin "3") (pinfunction "3_3") (pintype "passive"))
      (node (ref "U2") (pin "0.4") (pinfunction "P0_4_0.4") (pintype "bidirectional"))
    )
    (net (code "87") (name "VIN") (class "Default")
      (node (ref "C1") (pin "+") (pinfunction "+_+") (pintype "passive"))
      (node (ref "J14") (pin "2") (pinfunction "2_2") (pintype "passive"))
      (node (ref "J14") (pin "3") (pinfunction "3_3") (pintype "passive"))
      (node (ref "R2") (pin "2") (pinfunction "2_2") (pintype "passive"))
      (node (ref "U1") (pin "1") (pinfunction "VIN_1") (pintype "bidirectional"))
    )
    (net (code "88") (name "VIN_SCALED_IN") (class "Default")
      (node (ref "C2") (pin "1") (pinfunction "1_1") (pintype "passive"))
      (node (ref "R1") (pin "2") (pinfunction "2_2") (pintype "passive"))
      (node (ref "R2") (pin "1") (pinfunction "1_1") (pintype "passive"))
      (node (ref "U2") (pin "2.0") (pinfunction "P2_0_2.0") (pintype "bidirectional"))
    )
    (net (code "89") (name "WHEEL_ENCODER_A_IN") (class "Default")
      (node (ref "J17") (pin "3") (pinfunction "3_3") (pintype "passive"))
      (node (ref "U2") (pin "12.2") (pinfunction "P12_2_12.2") (pintype "bidirectional"))
    )
    (net (code "90") (name "WHEEL_ENCODER_B_IN") (class "Default")
      (node (ref "J17") (pin "2") (pinfunction "2_2") (pintype "passive"))
      (node (ref "U2") (pin "12.3") (pinfunction "P12_3_12.3") (pintype "bidirectional"))
    )
    (net (code "91") (name "X_DIRECTION_OUT") (class "Default")
      (node (ref "J1") (pin "1") (pinfunction "1_1") (pintype "passive"))
      (node (ref "U2") (pin "3.1") (pinfunction "P3_1_3.1") (pintype "bidirectional"))
    )
    (net (code "92") (name "X_LIMIT_IN") (class "Default")
      (node (ref "J1") (pin "3") (pinfunction "3_3") (pintype "passive"))
      (node (ref "U2") (pin "3.4") (pinfunction "P3_4_3.4") (pintype "bidirectional"))
    )
    (net (code "93") (name "X_STEP_OUT") (class "Default")
      (node (ref "J1") (pin "2") (pinfunction "2_2") (pintype "passive"))
      (node (ref "U2") (pin "3.3") (pinfunction "P3_3_3.3") (pintype "bidirectional"))
    )
    (net (code "94") (name "Y_DIRECTION_OUT") (class "Default")
      (node (ref "J2") (pin "1") (pinfunction "1_1") (pintype "passive"))
      (node (ref "U2") (pin "3.5") (pinfunction "P3_5_3.5") (pintype "bidirectional"))
    )
    (net (code "95") (name "Y_LIMIT_IN") (class "Default")
      (node (ref "J2") (pin "3") (pinfunction "3_3") (pintype "passive"))
      (node (ref "U2") (pin "3.7") (pinfunction "P3_7_3.7") (pintype "bidirectional"))
    )
    (net (code "96") (name "Y_STEP_OUT") (class "Default")
      (node (ref "J2") (pin "2") (pinfunction "2_2") (pintype "passive"))
      (node (ref "U2") (pin "3.6") (pinfunction "P3_6_3.6") (pintype "bidirectional"))
    )
    (net (code "97") (name "Z_DIRECTION_OUT") (class "Default")
      (node (ref "J3") (pin "1") (pinfunction "1_1") (pintype "passive"))
      (node (ref "U2") (pin "15.5") (pinfunction "P15_5_15.5") (pintype "bidirectional"))
    )
    (net (code "98") (name "Z_DISPLAY_RX_IN") (class "Default")
      (node (ref "J19") (pin "2") (pinfunction "2_2") (pintype "passive"))
      (node (ref "U2") (pin "2.5") (pinfunction "P2_5_2.5") (pintype "bidirectional"))
    )
    (net (code "99") (name "Z_DISPLAY_TX_OUT") (class "Default")
      (node (ref "J19") (pin "1") (pinfunction "1_1") (pintype "passive"))
      (node (ref "U2") (pin "2.6") (pinfunction "P2_6_2.6") (pintype "bidirectional"))
    )
    (net (code "100") (name "Z_LIMIT_IN") (class "Default")
      (node (ref "J3") (pin "3") (pinfunction "3_3") (pintype "passive"))
      (node (ref "U2") (pin "0.1") (pinfunction "P0_1_0.1") (pintype "bidirectional"))
    )
    (net (code "101") (name "Z_STEP_OUT") (class "Default")
      (node (ref "J3") (pin "2") (pinfunction "2_2") (pintype "passive"))
      (node (ref "U2") (pin "0.0") (pinfunction "P0_0_0.0") (pintype "bidirectional"))
    )
    (net (code "102") (name "unconnected-(U2-PadVCCIO)") (class "Default")
      (node (ref "U2") (pin "VCCIO") (pinfunction "VCCIO_VCCIO") (pintype "bidirectional"))
    )
    (net (code "103") (name "unconnected-(U2-PadXRES)") (class "Default")
      (node (ref "U2") (pin "XRES") (pinfunction "XRES_XRES") (pintype "bidirectional"))
    )
    (net (code "104") (name "unconnected-(U3-INTB-Pad19)") (class "Default")
      (node (ref "U3") (pin "19") (pinfunction "INTB_19") (pintype "output"))
    )
    (net (code "105") (name "unconnected-(U4-INTB-Pad19)") (class "Default")
      (node (ref "U4") (pin "19") (pinfunction "INTB_19") (pintype "output"))
    )
    (net (code "106") (name "unconnected-(WEMOS1-Pad3V3)") (class "Default")
      (node (ref "WEMOS1") (pin "3V3") (pinfunction "3V3_3V3") (pintype "bidirectional"))
    )
    (net (code "107") (name "unconnected-(WEMOS1-PadA0)") (class "Default")
      (node (ref "WEMOS1") (pin "A0") (pinfunction "A0_A0") (pintype "bidirectional"))
    )
    (net (code "108") (name "unconnected-(WEMOS1-PadD0)") (class "Default")
      (node (ref "WEMOS1") (pin "D0") (pinfunction "D0_D0") (pintype "bidirectional"))
    )
    (net (code "109") (name "unconnected-(WEMOS1-PadD1)") (class "Default")
      (node (ref "WEMOS1") (pin "D1") (pinfunction "D1_D1") (pintype "bidirectional"))
    )
    (net (code "110") (name "unconnected-(WEMOS1-PadD2)") (class "Default")
      (node (ref "WEMOS1") (pin "D2") (pinfunction "D2_D2") (pintype "bidirectional"))
    )
    (net (code "111") (name "unconnected-(WEMOS1-PadD3)") (class "Default")
      (node (ref "WEMOS1") (pin "D3") (pinfunction "D3_D3") (pintype "bidirectional"))
    )
    (net (code "112") (name "unconnected-(WEMOS1-PadD4)") (class "Default")
      (node (ref "WEMOS1") (pin "D4") (pinfunction "D4_D4") (pintype "bidirectional"))
    )
    (net (code "113") (name "unconnected-(WEMOS1-PadD5)") (class "Default")
      (node (ref "WEMOS1") (pin "D5") (pinfunction "D5_D5") (pintype "bidirectional"))
    )
    (net (code "114") (name "unconnected-(WEMOS1-PadD6)") (class "Default")
      (node (ref "WEMOS1") (pin "D6") (pinfunction "D6_D6") (pintype "bidirectional"))
    )
    (net (code "115") (name "unconnected-(WEMOS1-PadD7)") (class "Default")
      (node (ref "WEMOS1") (pin "D7") (pinfunction "D7_D7") (pintype "bidirectional"))
    )
    (net (code "116") (name "unconnected-(WEMOS1-PadD8)") (class "Default")
      (node (ref "WEMOS1") (pin "D8") (pinfunction "D8_D8") (pintype "bidirectional"))
    )
    (net (code "117") (name "unconnected-(WEMOS1-PadRESET)") (class "Default")
      (node (ref "WEMOS1") (pin "RESET") (pinfunction "RESET_RESET") (pintype "bidirectional"))
    )
  )
)
